# CG65_Schematics.net
KiCad netlist of a schematic drawn in Altium Designer
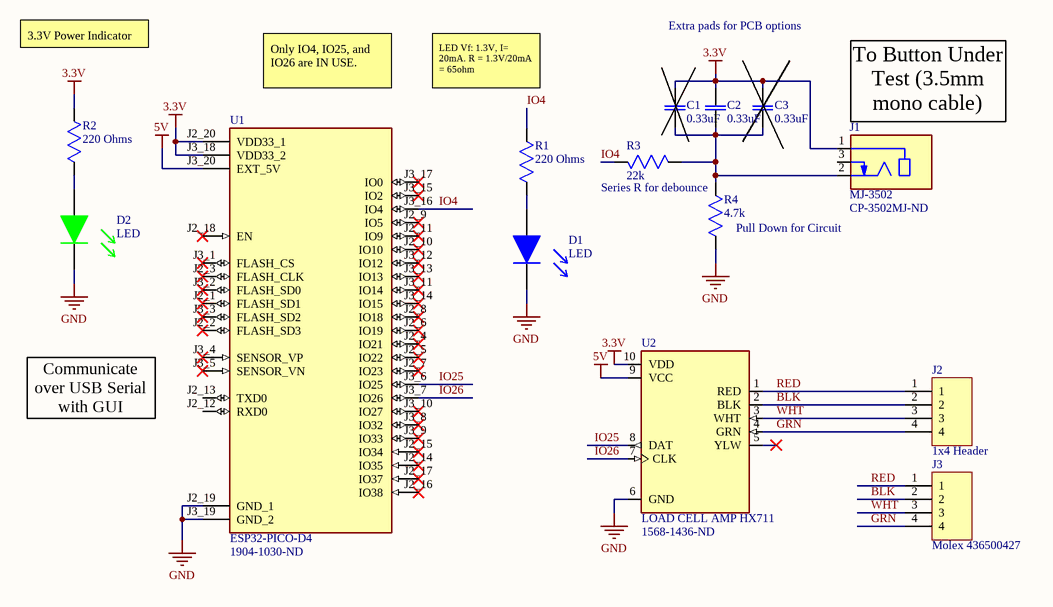
[diagram p0: CG65_Schematics.SchDoc]

(export (version "E")
  (design (tool "Eeschema 10.0.6"))
  (components
    (comp (ref "C1")
      (value "0.33uF")
      (footprint "TH CAPACITOR")
      (description "Standard Capacitor, Through Hole")
      (libsource (lib "SchematicLibrary") (part "Capacitor"))
    )
    (comp (ref "C2")
      (value "0.33uF")
      (footprint "TH CAPACITOR")
      (description "Standard Capacitor, Through Hole")
      (libsource (lib "SchematicLibrary") (part "Capacitor"))
    )
    (comp (ref "C3")
      (value "0.33uF")
      (footprint "TH CAPACITOR")
      (description "Standard Capacitor, Through Hole")
      (libsource (lib "SchematicLibrary") (part "Capacitor"))
    )
    (comp (ref "D1")
      (value "LED")
      (footprint "LED TH BLUE")
      (description "2V Blue LED Through Hole")
      (libsource (lib "SchematicLibrary") (part "LED Blue"))
    )
    (comp (ref "D2")
      (value "LED")
      (footprint "LED TH GREEN")
      (description "2V Green LED Through Hole")
      (libsource (lib "SchematicLibrary") (part "LED Green"))
    )
    (comp (ref "J1")
      (value "MJ-3502")
      (footprint "MJ-3502N")
      (description "3.5 mm, Mono, Right Angle, Through Hole, Threaded Bushing, Audio Jack Connector")
      (fields (field (name "MANUFACTURER") "CUI") (field (name "SUPPLIER PART NUMBER 1") "CP-3502MJ-ND"))
      (libsource (lib "SchematicLibrary") (part "MJ-3502"))
    )
    (comp (ref "J2")
      (value "1x4 Header")
      (footprint "1x4 Standard Header")
      (description "Standard 0.1\" Header 1x4")
      (libsource (lib "SchematicLibrary") (part "1x4 Header"))
    )
    (comp (ref "J3")
      (value "Molex 436500427")
      (footprint "MOLEX_436500427")
      (description "Molex MicroFit 3.0 Header 1x4, mates with 0436450400")
      (libsource (lib "SchematicLibrary") (part "Molex 436500427"))
    )
    (comp (ref "R1")
      (value "220 Ohms")
      (footprint "TH Resistor")
      (description "Standard Resistor, Through Hole, 1/8W")
      (libsource (lib "SchematicLibrary") (part "Resistor"))
    )
    (comp (ref "R2")
      (value "220 Ohms")
      (footprint "TH Resistor")
      (description "Standard Resistor, Through Hole, 1/8W")
      (libsource (lib "SchematicLibrary") (part "Resistor"))
    )
    (comp (ref "R3")
      (value "22k")
      (footprint "TH Resistor")
      (description "Standard Resistor, Through Hole, 1/8W")
      (libsource (lib "SchematicLibrary") (part "Resistor"))
    )
    (comp (ref "R4")
      (value "4.7k")
      (footprint "TH Resistor")
      (description "Standard Resistor, Through Hole, 1/8W")
      (libsource (lib "SchematicLibrary") (part "Resistor"))
    )
    (comp (ref "U1")
      (value "ESP32-PICO-D4")
      (footprint "ESP32-PICO-KIT")
      (description "ESP32 Wifi Bluetooth Eval Board")
      (fields
        (field (name "MANUFACTURER") "Espressif Systems")
        (field (name "MANUFACTURER PART NUMBER") "ESP32-PICO-KIT")
        (field (name "SUPPLIER PART NUMBER 1") "1904-1030-ND")
      )
      (libsource (lib "SchematicLibrary") (part "ESP32-PICO-KIT"))
    )
    (comp (ref "U2")
      (value "LOAD CELL AMP HX711")
      (footprint "SEN-13879")
      (description "HX711 Load Cell Amplifier")
      (fields
        (field (name "MANUFACTURER") "SparkFun")
        (field (name "MANUFACTURER PART NUMBER") "SEN-13879")
        (field (name "SUPPLIER PART NUMBER 1") "1568-1436-ND")
      )
      (libsource (lib "SchematicLibrary") (part "LOAD CELL AMP HX711"))
    )
  )
  (nets
    (net (code "1") (name "/BLK") (class "Default")
      (node (ref "J2") (pin "2") (pinfunction "2_2") (pintype "passive"))
      (node (ref "J3") (pin "2") (pinfunction "2_2") (pintype "passive"))
      (node (ref "U2") (pin "2") (pinfunction "BLK_2") (pintype "bidirectional"))
    )
    (net (code "2") (name "/GRN") (class "Default")
      (node (ref "J2") (pin "4") (pinfunction "4_4") (pintype "passive"))
      (node (ref "J3") (pin "4") (pinfunction "4_4") (pintype "passive"))
      (node (ref "U2") (pin "4") (pinfunction "GRN_4") (pintype "input"))
    )
    (net (code "3") (name "/IO4") (class "Default")
      (node (ref "R1") (pin "2") (pinfunction "R2_2") (pintype "passive"))
      (node (ref "R3") (pin "2") (pinfunction "R2_2") (pintype "passive"))
      (node (ref "U1") (pin "J3_16") (pinfunction "IO4_J3_16") (pintype "bidirectional"))
    )
    (net (code "4") (name "/IO25") (class "Default")
      (node (ref "U1") (pin "J3_6") (pinfunction "IO25_J3_6") (pintype "bidirectional"))
      (node (ref "U2") (pin "8") (pinfunction "DAT_8") (pintype "output"))
    )
    (net (code "5") (name "/IO26") (class "Default")
      (node (ref "U1") (pin "J3_7") (pinfunction "IO26_J3_7") (pintype "bidirectional"))
      (node (ref "U2") (pin "7") (pinfunction "CLK_7") (pintype "input"))
    )
    (net (code "6") (name "/RED") (class "Default")
      (node (ref "J2") (pin "1") (pinfunction "1_1") (pintype "passive"))
      (node (ref "J3") (pin "1") (pinfunction "1_1") (pintype "passive"))
      (node (ref "U2") (pin "1") (pinfunction "RED_1") (pintype "bidirectional"))
    )
    (net (code "7") (name "/WHT") (class "Default")
      (node (ref "J2") (pin "3") (pinfunction "3_3") (pintype "passive"))
      (node (ref "J3") (pin "3") (pinfunction "3_3") (pintype "passive"))
      (node (ref "U2") (pin "3") (pinfunction "WHT_3") (pintype "input"))
    )
    (net (code "8") (name "3.3V") (class "Default")
      (node (ref "C1") (pin "2") (pinfunction "2_2") (pintype "passive"))
      (node (ref "C2") (pin "2") (pinfunction "2_2") (pintype "passive"))
      (node (ref "C3") (pin "2") (pinfunction "2_2") (pintype "passive"))
      (node (ref "J1") (pin "1") (pinfunction "1_1") (pintype "passive"))
      (node (ref "R2") (pin "2") (pinfunction "R2_2") (pintype "passive"))
      (node (ref "U1") (pin "J2_20") (pinfunction "VDD33_1_J2_20") (pintype "power_in"))
      (node (ref "U1") (pin "J3_18") (pinfunction "VDD33_2_J3_18") (pintype "power_in"))
      (node (ref "U2") (pin "10") (pinfunction "VDD_10") (pintype "power_in"))
    )
    (net (code "9") (name "5V") (class "Default")
      (node (ref "U1") (pin "J3_20") (pinfunction "EXT_5V_J3_20") (pintype "power_in"))
      (node (ref "U2") (pin "9") (pinfunction "VCC_9") (pintype "power_in"))
    )
    (net (code "10") (name "GND") (class "Default")
      (node (ref "D1") (pin "1") (pinfunction "1_1") (pintype "passive"))
      (node (ref "D2") (pin "1") (pinfunction "1_1") (pintype "passive"))
      (node (ref "R4") (pin "1") (pinfunction "R1_1") (pintype "passive"))
      (node (ref "U1") (pin "J2_19") (pinfunction "GND_1_J2_19") (pintype "power_in"))
      (node (ref "U1") (pin "J3_19") (pinfunction "GND_2_J3_19") (pintype "power_in"))
      (node (ref "U2") (pin "6") (pinfunction "GND_6") (pintype "power_in"))
    )
    (net (code "11") (name "Net-(R1-R1)") (class "Default")
      (node (ref "D1") (pin "2") (pinfunction "2_2") (pintype "passive"))
      (node (ref "R1") (pin "1") (pinfunction "R1_1") (pintype "passive"))
    )
    (net (code "12") (name "Net-(R2-R1)") (class "Default")
      (node (ref "D2") (pin "2") (pinfunction "2_2") (pintype "passive"))
      (node (ref "R2") (pin "1") (pinfunction "R1_1") (pintype "passive"))
    )
    (net (code "13") (name "Net-(R3-R1)") (class "Default")
      (node (ref "C1") (pin "1") (pinfunction "1_1") (pintype "passive"))
      (node (ref "C2") (pin "1") (pinfunction "1_1") (pintype "passive"))
      (node (ref "C3") (pin "1") (pinfunction "1_1") (pintype "passive"))
      (node (ref "J1") (pin "2") (pinfunction "2_2") (pintype "passive"))
      (node (ref "R3") (pin "1") (pinfunction "R1_1") (pintype "passive"))
      (node (ref "R4") (pin "2") (pinfunction "R2_2") (pintype "passive"))
    )
    (net (code "14") (name "unconnected-(J1-Pad3)") (class "Default")
      (node (ref "J1") (pin "3") (pinfunction "3_3") (pintype "passive"))
    )
    (net (code "15") (name "unconnected-(U1-EN-PadJ2_18)") (class "Default")
      (node (ref "U1") (pin "J2_18") (pinfunction "EN_J2_18") (pintype "input+no_connect"))
    )
    (net (code "16") (name "unconnected-(U1-FLASH_CLK-PadJ2_3)") (class "Default")
      (node (ref "U1") (pin "J2_3") (pinfunction "FLASH_CLK_J2_3") (pintype "bidirectional+no_connect"))
    )
    (net (code "17") (name "unconnected-(U1-FLASH_CS-PadJ3_1)") (class "Default")
      (node (ref "U1") (pin "J3_1") (pinfunction "FLASH_CS_J3_1") (pintype "bidirectional+no_connect"))
    )
    (net (code "18") (name "unconnected-(U1-FLASH_SD0-PadJ3_2)") (class "Default")
      (node (ref "U1") (pin "J3_2") (pinfunction "FLASH_SD0_J3_2") (pintype "bidirectional+no_connect"))
    )
    (net (code "19") (name "unconnected-(U1-FLASH_SD1-PadJ2_1)") (class "Default")
      (node (ref "U1") (pin "J2_1") (pinfunction "FLASH_SD1_J2_1") (pintype "bidirectional+no_connect"))
    )
    (net (code "20") (name "unconnected-(U1-FLASH_SD2-PadJ3_3)") (class "Default")
      (node (ref "U1") (pin "J3_3") (pinfunction "FLASH_SD2_J3_3") (pintype "bidirectional+no_connect"))
    )
    (net (code "21") (name "unconnected-(U1-FLASH_SD3-PadJ2_2)") (class "Default")
      (node (ref "U1") (pin "J2_2") (pinfunction "FLASH_SD3_J2_2") (pintype "bidirectional+no_connect"))
    )
    (net (code "22") (name "unconnected-(U1-IO0-PadJ3_17)") (class "Default")
      (node (ref "U1") (pin "J3_17") (pinfunction "IO0_J3_17") (pintype "bidirectional+no_connect"))
    )
    (net (code "23") (name "unconnected-(U1-IO2-PadJ3_15)") (class "Default")
      (node (ref "U1") (pin "J3_15") (pinfunction "IO2_J3_15") (pintype "bidirectional+no_connect"))
    )
    (net (code "24") (name "unconnected-(U1-IO5-PadJ2_9)") (class "Default")
      (node (ref "U1") (pin "J2_9") (pinfunction "IO5_J2_9") (pintype "bidirectional+no_connect"))
    )
    (net (code "25") (name "unconnected-(U1-IO9-PadJ2_11)") (class "Default")
      (node (ref "U1") (pin "J2_11") (pinfunction "IO9_J2_11") (pintype "bidirectional+no_connect"))
    )
    (net (code "26") (name "unconnected-(U1-IO10-PadJ2_10)") (class "Default")
      (node (ref "U1") (pin "J2_10") (pinfunction "IO10_J2_10") (pintype "bidirectional+no_connect"))
    )
    (net (code "27") (name "unconnected-(U1-IO12-PadJ3_12)") (class "Default")
      (node (ref "U1") (pin "J3_12") (pinfunction "IO12_J3_12") (pintype "bidirectional+no_connect"))
    )
    (net (code "28") (name "unconnected-(U1-IO13-PadJ3_13)") (class "Default")
      (node (ref "U1") (pin "J3_13") (pinfunction "IO13_J3_13") (pintype "bidirectional+no_connect"))
    )
    (net (code "29") (name "unconnected-(U1-IO14-PadJ3_11)") (class "Default")
      (node (ref "U1") (pin "J3_11") (pinfunction "IO14_J3_11") (pintype "bidirectional+no_connect"))
    )
    (net (code "30") (name "unconnected-(U1-IO15-PadJ3_14)") (class "Default")
      (node (ref "U1") (pin "J3_14") (pinfunction "IO15_J3_14") (pintype "bidirectional+no_connect"))
    )
    (net (code "31") (name "unconnected-(U1-IO18-PadJ2_8)") (class "Default")
      (node (ref "U1") (pin "J2_8") (pinfunction "IO18_J2_8") (pintype "bidirectional+no_connect"))
    )
    (net (code "32") (name "unconnected-(U1-IO19-PadJ2_6)") (class "Default")
      (node (ref "U1") (pin "J2_6") (pinfunction "IO19_J2_6") (pintype "bidirectional+no_connect"))
    )
    (net (code "33") (name "unconnected-(U1-IO21-PadJ2_4)") (class "Default")
      (node (ref "U1") (pin "J2_4") (pinfunction "IO21_J2_4") (pintype "bidirectional+no_connect"))
    )
    (net (code "34") (name "unconnected-(U1-IO22-PadJ2_5)") (class "Default")
      (node (ref "U1") (pin "J2_5") (pinfunction "IO22_J2_5") (pintype "bidirectional+no_connect"))
    )
    (net (code "35") (name "unconnected-(U1-IO23-PadJ2_7)") (class "Default")
      (node (ref "U1") (pin "J2_7") (pinfunction "IO23_J2_7") (pintype "bidirectional+no_connect"))
    )
    (net (code "36") (name "unconnected-(U1-IO27-PadJ3_10)") (class "Default")
      (node (ref "U1") (pin "J3_10") (pinfunction "IO27_J3_10") (pintype "bidirectional+no_connect"))
    )
    (net (code "37") (name "unconnected-(U1-IO32-PadJ3_8)") (class "Default")
      (node (ref "U1") (pin "J3_8") (pinfunction "IO32_J3_8") (pintype "bidirectional+no_connect"))
    )
    (net (code "38") (name "unconnected-(U1-IO33-PadJ3_9)") (class "Default")
      (node (ref "U1") (pin "J3_9") (pinfunction "IO33_J3_9") (pintype "bidirectional+no_connect"))
    )
    (net (code "39") (name "unconnected-(U1-IO34-PadJ2_15)") (class "Default")
      (node (ref "U1") (pin "J2_15") (pinfunction "IO34_J2_15") (pintype "input+no_connect"))
    )
    (net (code "40") (name "unconnected-(U1-IO35-PadJ2_14)") (class "Default")
      (node (ref "U1") (pin "J2_14") (pinfunction "IO35_J2_14") (pintype "input+no_connect"))
    )
    (net (code "41") (name "unconnected-(U1-IO37-PadJ2_17)") (class "Default")
      (node (ref "U1") (pin "J2_17") (pinfunction "IO37_J2_17") (pintype "input+no_connect"))
    )
    (net (code "42") (name "unconnected-(U1-IO38-PadJ2_16)") (class "Default")
      (node (ref "U1") (pin "J2_16") (pinfunction "IO38_J2_16") (pintype "input+no_connect"))
    )
    (net (code "43") (name "unconnected-(U1-RXD0-PadJ2_12)") (class "Default")
      (node (ref "U1") (pin "J2_12") (pinfunction "RXD0_J2_12") (pintype "bidirectional"))
    )
    (net (code "44") (name "unconnected-(U1-SENSOR_VN-PadJ3_5)") (class "Default")
      (node (ref "U1") (pin "J3_5") (pinfunction "SENSOR_VN_J3_5") (pintype "input+no_connect"))
    )
    (net (code "45") (name "unconnected-(U1-SENSOR_VP-PadJ3_4)") (class "Default")
      (node (ref "U1") (pin "J3_4") (pinfunction "SENSOR_VP_J3_4") (pintype "input+no_connect"))
    )
    (net (code "46") (name "unconnected-(U1-TXD0-PadJ2_13)") (class "Default")
      (node (ref "U1") (pin "J2_13") (pinfunction "TXD0_J2_13") (pintype "bidirectional"))
    )
    (net (code "47") (name "unconnected-(U2-YLW-Pad5)") (class "Default")
      (node (ref "U2") (pin "5") (pinfunction "YLW_5") (pintype "bidirectional+no_connect"))
    )
  )
)
